# 3.net
KiCad netlist of a schematic drawn in Altium Designer
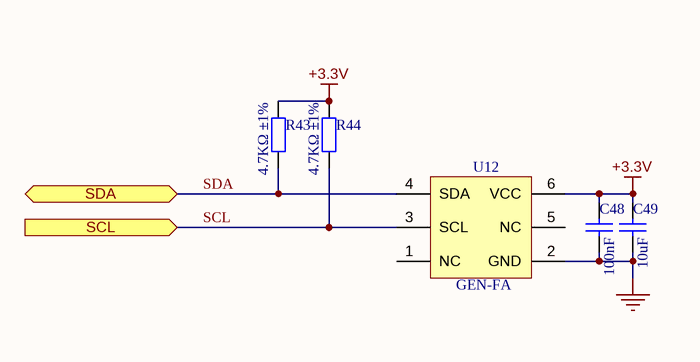
[diagram p0: 3_电子天平_加密芯片.SchDoc]

(export (version "E")
  (design (tool "Eeschema 10.0.6"))
  (components
    (comp (ref "C48")
      (value "100nF")
      (footprint "LC-0805_C")
      (description "MLCC")
      (fields (field (name "PUBLISHER") "Altium Limited"))
      (libsource (lib "Miscellaneous Devices") (part "Cap"))
    )
    (comp (ref "C49")
      (value "10uF")
      (footprint "LC-0805_C")
      (description "MLCC")
      (fields (field (name "PUBLISHER") "Altium Limited"))
      (libsource (lib "Miscellaneous Devices") (part "Cap"))
    )
    (comp (ref "R43")
      (value "4.7KΩ ±1%")
      (footprint "LC-0805_R")
      (description "Resistor")
      (fields (field (name "PUBLISHER") "Altium Limited"))
      (libsource (lib "Miscellaneous Devices") (part "Res2"))
    )
    (comp (ref "R44")
      (value "4.7KΩ ±1%")
      (footprint "LC-0805_R")
      (description "Resistor")
      (fields (field (name "PUBLISHER") "Altium Limited"))
      (libsource (lib "Miscellaneous Devices") (part "Res2"))
    )
    (comp (ref "U12")
      (value "GEN-FA")
      (footprint "LC-SOT-23-6")
      (description "neowine加密芯片  带32Kbits EEPROM。")
      (libsource (lib "Riggin") (part "ALPU-FA"))
    )
  )
  (nets
    (net (code "1") (name "+3.3V") (class "Default")
      (node (ref "C48") (pin "1") (pinfunction "1_1") (pintype "passive"))
      (node (ref "C49") (pin "1") (pinfunction "1_1") (pintype "passive"))
      (node (ref "R43") (pin "1") (pinfunction "1_1") (pintype "passive"))
      (node (ref "R44") (pin "1") (pinfunction "1_1") (pintype "passive"))
      (node (ref "U12") (pin "6") (pinfunction "VCC_6") (pintype "passive"))
    )
    (net (code "2") (name "/SCL") (class "Default")
      (node (ref "R44") (pin "2") (pinfunction "2_2") (pintype "passive"))
      (node (ref "U12") (pin "3") (pinfunction "SCL_3") (pintype "passive"))
    )
    (net (code "3") (name "/SDA") (class "Default")
      (node (ref "R43") (pin "2") (pinfunction "2_2") (pintype "passive"))
      (node (ref "U12") (pin "4") (pinfunction "SDA_4") (pintype "passive"))
    )
    (net (code "4") (name "GND") (class "Default")
      (node (ref "C48") (pin "2") (pinfunction "2_2") (pintype "passive"))
      (node (ref "C49") (pin "2") (pinfunction "2_2") (pintype "passive"))
      (node (ref "U12") (pin "2") (pinfunction "GND_2") (pintype "passive"))
    )
    (net (code "5") (name "unconnected-(U12-NC-Pad1)") (class "Default")
      (node (ref "U12") (pin "1") (pinfunction "NC_1") (pintype "passive"))
    )
    (net (code "6") (name "unconnected-(U12-NC-Pad5)") (class "Default")
      (node (ref "U12") (pin "5") (pinfunction "NC_5") (pintype "passive"))
    )
  )
)
